# JacdacHub_39.net
KiCad netlist of a schematic drawn in Altium Designer
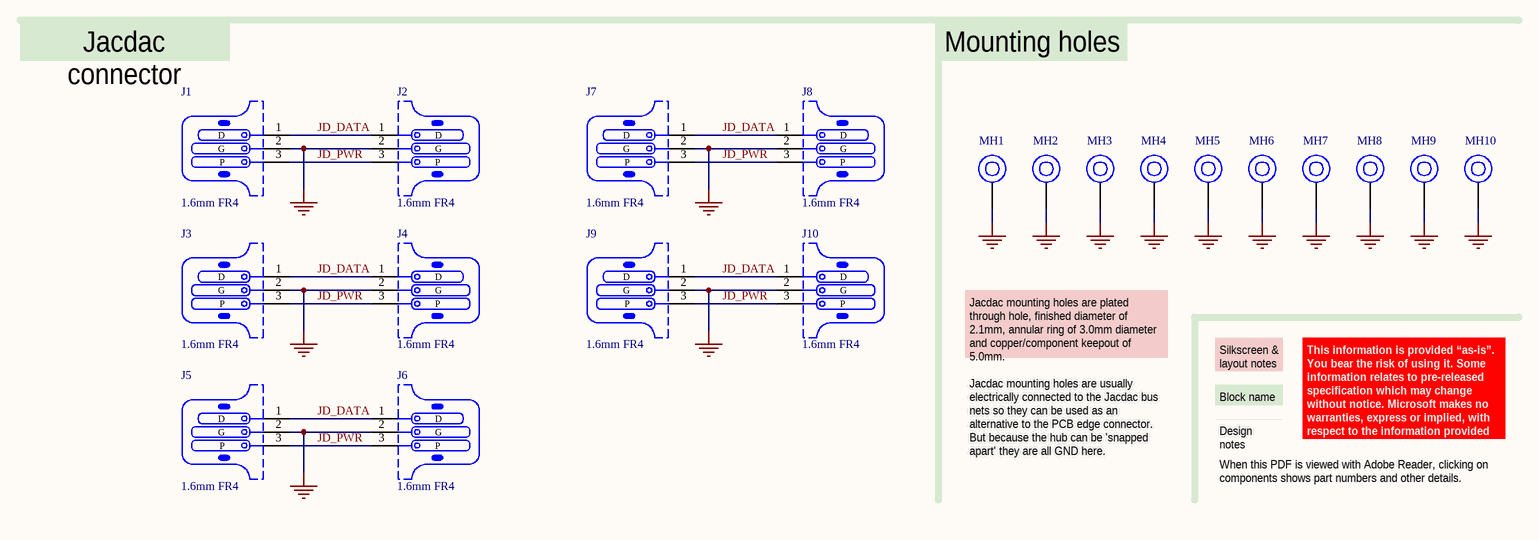
[diagram p0: JacdacHub 39.SchDoc]

(export (version "E")
  (design (tool "Eeschema 10.0.6"))
  (components
    (comp (ref "J1")
      (value "3 pin JACDAC edge connector")
      (footprint "JACDAC_EDGE_CONNECTOR_NO_TRACES")
      (description "3 pin Jacdac edge connector 1.27mm pitch")
      (fields
        (field (name "MANUFACTURER PART NUMBER") "JACDAC_EDGE_CONNECTOR")
        (field (name "PCB TYPE") "1.6mm FR4")
        (field (name "CHECKED BY") "?")
        (field (name "CREATED BY") "D. Gakure")
      )
      (libsource (lib "generic-con") (part "Jacdac edge connector"))
    )
    (comp (ref "J2")
      (value "3 pin JACDAC edge connector")
      (footprint "JACDAC_EDGE_CONNECTOR_NO_TRACES")
      (description "3 pin Jacdac edge connector 1.27mm pitch")
      (fields
        (field (name "MANUFACTURER PART NUMBER") "JACDAC_EDGE_CONNECTOR")
        (field (name "PCB TYPE") "1.6mm FR4")
        (field (name "CHECKED BY") "?")
        (field (name "CREATED BY") "D. Gakure")
      )
      (libsource (lib "") (part "Jacdac edge connector_1"))
    )
    (comp (ref "J3")
      (value "3 pin JACDAC edge connector")
      (footprint "JACDAC_EDGE_CONNECTOR_NO_TRACES")
      (description "3 pin Jacdac edge connector 1.27mm pitch")
      (fields
        (field (name "MANUFACTURER PART NUMBER") "JACDAC_EDGE_CONNECTOR")
        (field (name "PCB TYPE") "1.6mm FR4")
        (field (name "CHECKED BY") "?")
        (field (name "CREATED BY") "D. Gakure")
      )
      (libsource (lib "generic-con") (part "Jacdac edge connector"))
    )
    (comp (ref "J4")
      (value "3 pin JACDAC edge connector")
      (footprint "JACDAC_EDGE_CONNECTOR_NO_TRACES")
      (description "3 pin Jacdac edge connector 1.27mm pitch")
      (fields
        (field (name "MANUFACTURER PART NUMBER") "JACDAC_EDGE_CONNECTOR")
        (field (name "PCB TYPE") "1.6mm FR4")
        (field (name "CHECKED BY") "?")
        (field (name "CREATED BY") "D. Gakure")
      )
      (libsource (lib "") (part "Jacdac edge connector_1"))
    )
    (comp (ref "J5")
      (value "3 pin JACDAC edge connector")
      (footprint "JACDAC_EDGE_CONNECTOR_NO_TRACES")
      (description "3 pin Jacdac edge connector 1.27mm pitch")
      (fields
        (field (name "MANUFACTURER PART NUMBER") "JACDAC_EDGE_CONNECTOR")
        (field (name "PCB TYPE") "1.6mm FR4")
        (field (name "CHECKED BY") "?")
        (field (name "CREATED BY") "D. Gakure")
      )
      (libsource (lib "generic-con") (part "Jacdac edge connector"))
    )
    (comp (ref "J6")
      (value "3 pin JACDAC edge connector")
      (footprint "JACDAC_EDGE_CONNECTOR_NO_TRACES")
      (description "3 pin Jacdac edge connector 1.27mm pitch")
      (fields
        (field (name "MANUFACTURER PART NUMBER") "JACDAC_EDGE_CONNECTOR")
        (field (name "PCB TYPE") "1.6mm FR4")
        (field (name "CHECKED BY") "?")
        (field (name "CREATED BY") "D. Gakure")
      )
      (libsource (lib "") (part "Jacdac edge connector_1"))
    )
    (comp (ref "J7")
      (value "3 pin JACDAC edge connector")
      (footprint "JACDAC_EDGE_CONNECTOR_NO_TRACES")
      (description "3 pin Jacdac edge connector 1.27mm pitch")
      (fields
        (field (name "MANUFACTURER PART NUMBER") "JACDAC_EDGE_CONNECTOR")
        (field (name "PCB TYPE") "1.6mm FR4")
        (field (name "CHECKED BY") "?")
        (field (name "CREATED BY") "D. Gakure")
      )
      (libsource (lib "generic-con") (part "Jacdac edge connector"))
    )
    (comp (ref "J8")
      (value "3 pin JACDAC edge connector")
      (footprint "JACDAC_EDGE_CONNECTOR_NO_TRACES")
      (description "3 pin Jacdac edge connector 1.27mm pitch")
      (fields
        (field (name "MANUFACTURER PART NUMBER") "JACDAC_EDGE_CONNECTOR")
        (field (name "PCB TYPE") "1.6mm FR4")
        (field (name "CHECKED BY") "?")
        (field (name "CREATED BY") "D. Gakure")
      )
      (libsource (lib "") (part "Jacdac edge connector_1"))
    )
    (comp (ref "J9")
      (value "3 pin JACDAC edge connector")
      (footprint "JACDAC_EDGE_CONNECTOR_NO_TRACES")
      (description "3 pin Jacdac edge connector 1.27mm pitch")
      (fields
        (field (name "MANUFACTURER PART NUMBER") "JACDAC_EDGE_CONNECTOR")
        (field (name "PCB TYPE") "1.6mm FR4")
        (field (name "CHECKED BY") "?")
        (field (name "CREATED BY") "D. Gakure")
      )
      (libsource (lib "generic-con") (part "Jacdac edge connector"))
    )
    (comp (ref "J10")
      (value "3 pin JACDAC edge connector")
      (footprint "JACDAC_EDGE_CONNECTOR_NO_TRACES")
      (description "3 pin Jacdac edge connector 1.27mm pitch")
      (fields
        (field (name "MANUFACTURER PART NUMBER") "JACDAC_EDGE_CONNECTOR")
        (field (name "PCB TYPE") "1.6mm FR4")
        (field (name "CHECKED BY") "?")
        (field (name "CREATED BY") "D. Gakure")
      )
      (libsource (lib "") (part "Jacdac edge connector_1"))
    )
    (comp (ref "MH1")
      (value "MH_5.0MMK_3.0MMC_2.1MMD_PTH")
      (footprint "MH_5.0MMK_3.0MMC_2.1MMD_PTH_NO_NOTES")
      (description "Mounting Hole 5.0mm keepout, 3.0mm annualar ring and 2.1mm Drill PTH")
      (libsource (lib "generic") (part "MH_5.0MMK_3.0MMC_2.1MMD_PTH"))
    )
    (comp (ref "MH2")
      (value "MH_5.0MMK_3.0MMC_2.1MMD_PTH")
      (footprint "MH_5.0MMK_3.0MMC_2.1MMD_PTH_NO_NOTES")
      (description "Mounting Hole 5.0mm keepout, 3.0mm annualar ring and 2.1mm Drill PTH")
      (libsource (lib "generic") (part "MH_5.0MMK_3.0MMC_2.1MMD_PTH"))
    )
    (comp (ref "MH3")
      (value "MH_5.0MMK_3.0MMC_2.1MMD_PTH")
      (footprint "MH_5.0MMK_3.0MMC_2.1MMD_PTH_NO_NOTES")
      (description "Mounting Hole 5.0mm keepout, 3.0mm annualar ring and 2.1mm Drill PTH")
      (libsource (lib "generic") (part "MH_5.0MMK_3.0MMC_2.1MMD_PTH"))
    )
    (comp (ref "MH4")
      (value "MH_5.0MMK_3.0MMC_2.1MMD_PTH")
      (footprint "MH_5.0MMK_3.0MMC_2.1MMD_PTH_NO_NOTES")
      (description "Mounting Hole 5.0mm keepout, 3.0mm annualar ring and 2.1mm Drill PTH")
      (libsource (lib "generic") (part "MH_5.0MMK_3.0MMC_2.1MMD_PTH"))
    )
    (comp (ref "MH5")
      (value "MH_5.0MMK_3.0MMC_2.1MMD_PTH")
      (footprint "MH_5.0MMK_3.0MMC_2.1MMD_PTH_NO_NOTES")
      (description "Mounting Hole 5.0mm keepout, 3.0mm annualar ring and 2.1mm Drill PTH")
      (libsource (lib "generic") (part "MH_5.0MMK_3.0MMC_2.1MMD_PTH"))
    )
    (comp (ref "MH6")
      (value "MH_5.0MMK_3.0MMC_2.1MMD_PTH")
      (footprint "MH_5.0MMK_3.0MMC_2.1MMD_PTH_NO_NOTES")
      (description "Mounting Hole 5.0mm keepout, 3.0mm annualar ring and 2.1mm Drill PTH")
      (libsource (lib "generic") (part "MH_5.0MMK_3.0MMC_2.1MMD_PTH"))
    )
    (comp (ref "MH7")
      (value "MH_5.0MMK_3.0MMC_2.1MMD_PTH")
      (footprint "MH_5.0MMK_3.0MMC_2.1MMD_PTH_NO_NOTES")
      (description "Mounting Hole 5.0mm keepout, 3.0mm annualar ring and 2.1mm Drill PTH")
      (libsource (lib "generic") (part "MH_5.0MMK_3.0MMC_2.1MMD_PTH"))
    )
    (comp (ref "MH8")
      (value "MH_5.0MMK_3.0MMC_2.1MMD_PTH")
      (footprint "MH_5.0MMK_3.0MMC_2.1MMD_PTH_NO_NOTES")
      (description "Mounting Hole 5.0mm keepout, 3.0mm annualar ring and 2.1mm Drill PTH")
      (libsource (lib "generic") (part "MH_5.0MMK_3.0MMC_2.1MMD_PTH"))
    )
    (comp (ref "MH9")
      (value "MH_5.0MMK_3.0MMC_2.1MMD_PTH")
      (footprint "MH_5.0MMK_3.0MMC_2.1MMD_PTH_NO_NOTES")
      (description "Mounting Hole 5.0mm keepout, 3.0mm annualar ring and 2.1mm Drill PTH")
      (libsource (lib "generic") (part "MH_5.0MMK_3.0MMC_2.1MMD_PTH"))
    )
    (comp (ref "MH10")
      (value "MH_5.0MMK_3.0MMC_2.1MMD_PTH")
      (footprint "MH_5.0MMK_3.0MMC_2.1MMD_PTH_NO_NOTES")
      (description "Mounting Hole 5.0mm keepout, 3.0mm annualar ring and 2.1mm Drill PTH")
      (libsource (lib "generic") (part "MH_5.0MMK_3.0MMC_2.1MMD_PTH"))
    )
  )
  (nets
    (net (code "1") (name "/JD_DATA") (class "Default")
      (node (ref "J1") (pin "1") (pinfunction "D_1") (pintype "passive"))
      (node (ref "J10") (pin "1") (pinfunction "D_1") (pintype "passive"))
      (node (ref "J2") (pin "1") (pinfunction "D_1") (pintype "passive"))
      (node (ref "J3") (pin "1") (pinfunction "D_1") (pintype "passive"))
      (node (ref "J4") (pin "1") (pinfunction "D_1") (pintype "passive"))
      (node (ref "J5") (pin "1") (pinfunction "D_1") (pintype "passive"))
      (node (ref "J6") (pin "1") (pinfunction "D_1") (pintype "passive"))
      (node (ref "J7") (pin "1") (pinfunction "D_1") (pintype "passive"))
      (node (ref "J8") (pin "1") (pinfunction "D_1") (pintype "passive"))
      (node (ref "J9") (pin "1") (pinfunction "D_1") (pintype "passive"))
    )
    (net (code "2") (name "/JD_PWR") (class "Default")
      (node (ref "J1") (pin "3") (pinfunction "P_3") (pintype "passive"))
      (node (ref "J10") (pin "3") (pinfunction "P_3") (pintype "passive"))
      (node (ref "J2") (pin "3") (pinfunction "P_3") (pintype "passive"))
      (node (ref "J3") (pin "3") (pinfunction "P_3") (pintype "passive"))
      (node (ref "J4") (pin "3") (pinfunction "P_3") (pintype "passive"))
      (node (ref "J5") (pin "3") (pinfunction "P_3") (pintype "passive"))
      (node (ref "J6") (pin "3") (pinfunction "P_3") (pintype "passive"))
      (node (ref "J7") (pin "3") (pinfunction "P_3") (pintype "passive"))
      (node (ref "J8") (pin "3") (pinfunction "P_3") (pintype "passive"))
      (node (ref "J9") (pin "3") (pinfunction "P_3") (pintype "passive"))
    )
    (net (code "3") (name "GND") (class "Default")
      (node (ref "J1") (pin "2") (pinfunction "G_2") (pintype "passive"))
      (node (ref "J10") (pin "2") (pinfunction "G_2") (pintype "passive"))
      (node (ref "J2") (pin "2") (pinfunction "G_2") (pintype "passive"))
      (node (ref "J3") (pin "2") (pinfunction "G_2") (pintype "passive"))
      (node (ref "J4") (pin "2") (pinfunction "G_2") (pintype "passive"))
      (node (ref "J5") (pin "2") (pinfunction "G_2") (pintype "passive"))
      (node (ref "J6") (pin "2") (pinfunction "G_2") (pintype "passive"))
      (node (ref "J7") (pin "2") (pinfunction "G_2") (pintype "passive"))
      (node (ref "J8") (pin "2") (pinfunction "G_2") (pintype "passive"))
      (node (ref "J9") (pin "2") (pinfunction "G_2") (pintype "passive"))
      (node (ref "MH1") (pin "1") (pinfunction "1_1") (pintype "passive"))
      (node (ref "MH10") (pin "1") (pinfunction "1_1") (pintype "passive"))
      (node (ref "MH2") (pin "1") (pinfunction "1_1") (pintype "passive"))
      (node (ref "MH3") (pin "1") (pinfunction "1_1") (pintype "passive"))
      (node (ref "MH4") (pin "1") (pinfunction "1_1") (pintype "passive"))
      (node (ref "MH5") (pin "1") (pinfunction "1_1") (pintype "passive"))
      (node (ref "MH6") (pin "1") (pinfunction "1_1") (pintype "passive"))
      (node (ref "MH7") (pin "1") (pinfunction "1_1") (pintype "passive"))
      (node (ref "MH8") (pin "1") (pinfunction "1_1") (pintype "passive"))
      (node (ref "MH9") (pin "1") (pinfunction "1_1") (pintype "passive"))
    )
  )
)
